# 05_SD_USB.net
KiCad netlist of a schematic drawn in Altium Designer
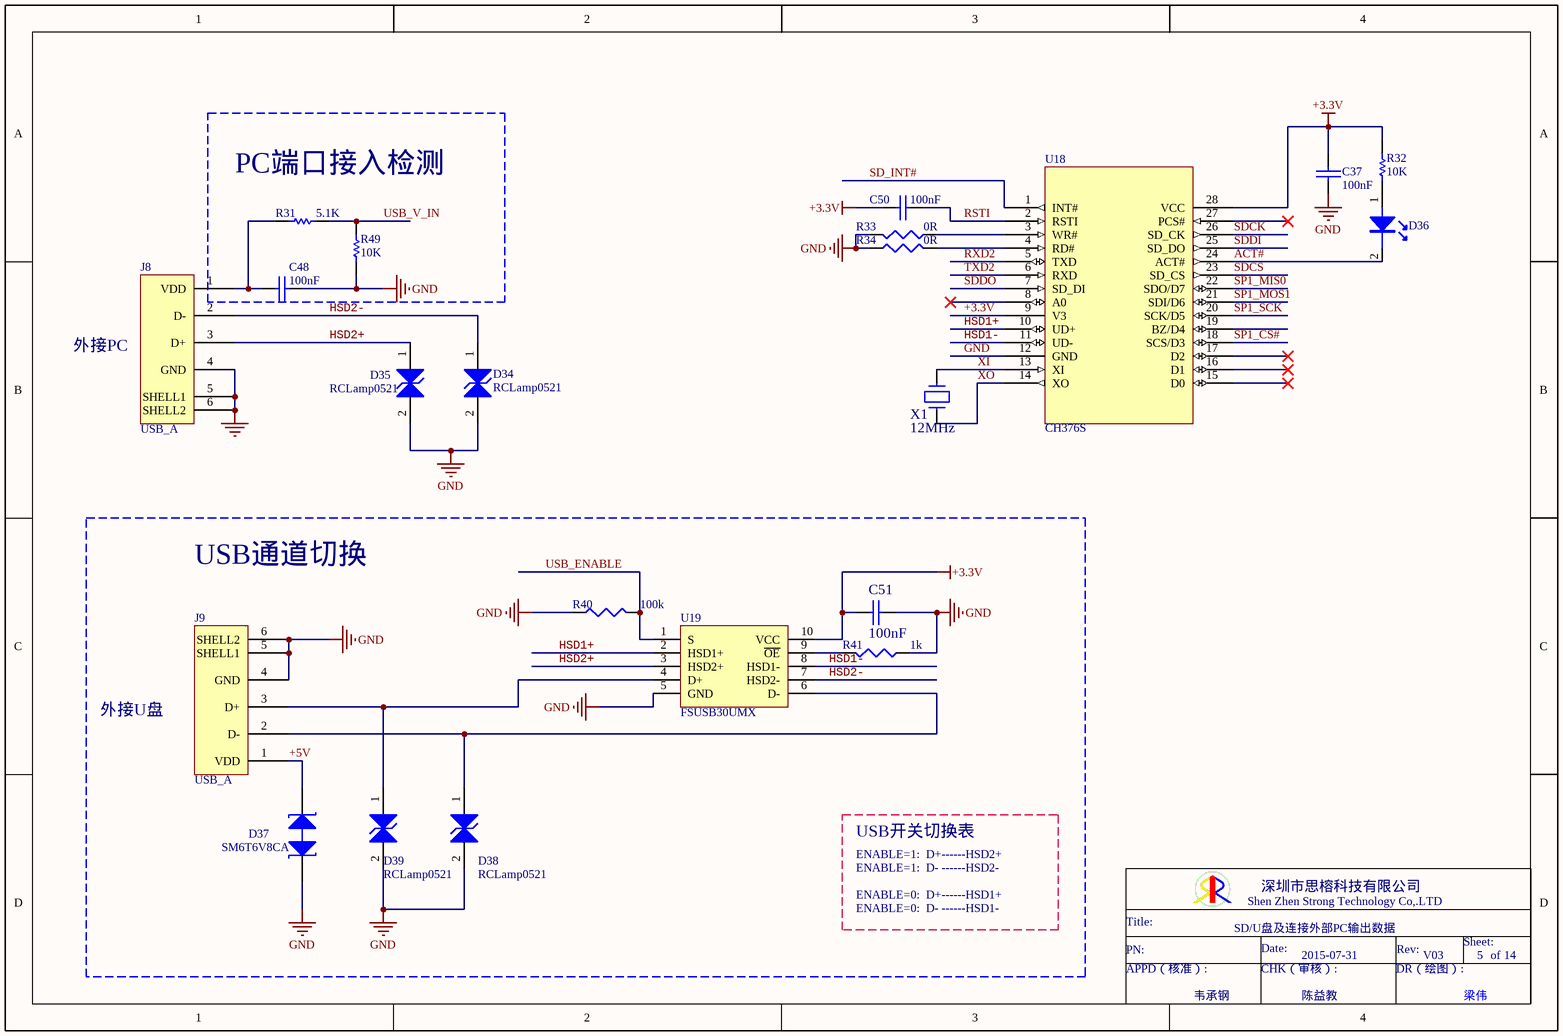
[diagram p0: 05_SD_USB.SchDoc]

(export (version "E")
  (design (tool "Eeschema 10.0.6"))
  (components
    (comp (ref "C37")
      (value "100nF")
      (footprint "0603C")
      (description "Capacitor")
      (libsource (lib "*") (part "CAP"))
    )
    (comp (ref "C48")
      (value "100nF")
      (footprint "0603C")
      (description "Capacitor")
      (libsource (lib "Mylibrary") (part "CAP"))
    )
    (comp (ref "C50")
      (value "100nF")
      (footprint "0603C")
      (description "Capacitor")
      (libsource (lib "Mylibrary") (part "CAP"))
    )
    (comp (ref "C51") (value "100nF") (footprint "0603C") (libsource (lib "*") (part "Pro7B.tmp_0.01u_17")))
    (comp (ref "D34")
      (value "RCLamp0521")
      (footprint "TVS")
      (description "RCLamp0521   SEMTECH")
      (fields (field (name "PUBLISHER") "Altium Limited"))
      (libsource (lib "LGA") (part "TVS"))
    )
    (comp (ref "D35")
      (value "RCLamp0521")
      (footprint "TVS")
      (description "RCLamp0521   SEMTECH")
      (fields (field (name "PUBLISHER") "Altium Limited"))
      (libsource (lib "LGA") (part "TVS"))
    )
    (comp (ref "D36")
      (value "LED灯 白发红光")
      (footprint "D0603")
      (description "LED灯")
      (libsource (lib "Mylibrary") (part "LED"))
    )
    (comp (ref "D37")
      (value "SM6T6V8CA")
      (footprint "DO-214AA")
      (description "SM6T6V8CA  ST")
      (fields (field (name "PUBLISHER") "Altium Limited"))
      (libsource (lib "Mylibrary") (part "TVS-1"))
    )
    (comp (ref "D38")
      (value "RCLamp0521")
      (footprint "TVS")
      (description "RCLamp0521   SEMTECH")
      (fields (field (name "PUBLISHER") "Altium Limited"))
      (libsource (lib "LGA") (part "TVS"))
    )
    (comp (ref "D39")
      (value "RCLamp0521")
      (footprint "TVS")
      (description "RCLamp0521   SEMTECH")
      (fields (field (name "PUBLISHER") "Altium Limited"))
      (libsource (lib "LGA") (part "TVS"))
    )
    (comp (ref "J8") (value "USB_A") (footprint "USB-AF") (libsource (lib "*") (part "USB")))
    (comp (ref "J9") (value "USB_A") (footprint "USB-AF") (libsource (lib "") (part "USB_1")))
    (comp (ref "R31") (value "5.1K") (footprint "0603R") (libsource (lib "Mylibrary") (part "RES")))
    (comp (ref "R32") (value "10K") (footprint "0603R") (libsource (lib "Mylibrary") (part "RES")))
    (comp (ref "R33") (value "0R") (footprint "0603R") (libsource (lib "LGA") (part "RES1")))
    (comp (ref "R34") (value "0R") (footprint "0603R") (libsource (lib "LGA") (part "RES1")))
    (comp (ref "R40") (value "100k") (footprint "0603R") (libsource (lib "Mylibrary") (part "RES1")))
    (comp (ref "R41") (value "1k") (footprint "0603R") (libsource (lib "Mylibrary") (part "RES1")))
    (comp (ref "R49") (value "10K") (footprint "0603R") (libsource (lib "Mylibrary") (part "RES")))
    (comp (ref "U18")
      (value "CH376S")
      (footprint "SOP28")
      (description "USB Host and SD card Host with File System & USB Device for MCU, parallel / SPI / UART Serial")
      (libsource (lib "*") (part "CH376S"))
    )
    (comp (ref "U19")
      (value "FSUSB30UMX")
      (footprint "SSOP10")
      (description "USB开关")
      (libsource (lib "Mylibrary") (part "FSUSB30UMX_1"))
    )
    (comp (ref "X1") (value "12MHz") (footprint "CRYL3*5") (libsource (lib "*") (part "Pro7B.tmp_12MHz_19")))
  )
  (nets
    (net (code "1") (name "+3.3V") (class "Default")
      (node (ref "C37") (pin "1") (pinfunction "1_1") (pintype "passive"))
      (node (ref "C50") (pin "1") (pinfunction "1_1") (pintype "passive"))
      (node (ref "C51") (pin "1") (pintype "passive"))
      (node (ref "R32") (pin "2") (pinfunction "2_2") (pintype "passive"))
      (node (ref "U18") (pin "28") (pinfunction "VCC_28") (pintype "power_in"))
      (node (ref "U18") (pin "9") (pinfunction "V3_9") (pintype "power_in"))
      (node (ref "U19") (pin "10") (pinfunction "VCC_10") (pintype "power_in"))
    )
    (net (code "2") (name "/+5V") (class "Default")
      (node (ref "D37") (pin "2") (pinfunction "2_2") (pintype "passive"))
      (node (ref "J9") (pin "1") (pinfunction "VDD_1") (pintype "passive"))
    )
    (net (code "3") (name "/ACT#") (class "Default")
      (node (ref "D36") (pin "2") (pinfunction "2_2") (pintype "passive"))
      (node (ref "U18") (pin "24") (pinfunction "ACT#_24") (pintype "output"))
    )
    (net (code "4") (name "/HSD1+") (class "Default")
      (node (ref "U18") (pin "10") (pinfunction "UD+_10") (pintype "bidirectional"))
      (node (ref "U19") (pin "2") (pinfunction "HSD1+_2") (pintype "passive"))
    )
    (net (code "5") (name "/HSD1-") (class "Default")
      (node (ref "U18") (pin "11") (pinfunction "UD-_11") (pintype "bidirectional"))
      (node (ref "U19") (pin "8") (pinfunction "HSD1-_8") (pintype "passive"))
    )
    (net (code "6") (name "/HSD2+") (class "Default")
      (node (ref "D35") (pin "1") (pinfunction "1_1") (pintype "passive"))
      (node (ref "J8") (pin "3") (pinfunction "D+_3") (pintype "passive"))
      (node (ref "U19") (pin "3") (pinfunction "HSD2+_3") (pintype "passive"))
    )
    (net (code "7") (name "/HSD2-") (class "Default")
      (node (ref "D34") (pin "1") (pinfunction "1_1") (pintype "passive"))
      (node (ref "J8") (pin "2") (pinfunction "D-_2") (pintype "passive"))
      (node (ref "U19") (pin "7") (pinfunction "HSD2-_7") (pintype "passive"))
    )
    (net (code "8") (name "/RSTI") (class "Default")
      (node (ref "C50") (pin "2") (pinfunction "2_2") (pintype "passive"))
      (node (ref "U18") (pin "2") (pinfunction "RSTI_2") (pintype "input"))
    )
    (net (code "9") (name "/RXD2") (class "Default")
      (node (ref "U18") (pin "5") (pinfunction "TXD_5") (pintype "bidirectional"))
    )
    (net (code "10") (name "/SDCK") (class "Default")
      (node (ref "U18") (pin "26") (pinfunction "SD_CK_26") (pintype "output"))
    )
    (net (code "11") (name "/SDCS") (class "Default")
      (node (ref "U18") (pin "23") (pinfunction "SD_CS_23") (pintype "output"))
    )
    (net (code "12") (name "/SDDI") (class "Default")
      (node (ref "U18") (pin "25") (pinfunction "SD_DO_25") (pintype "output"))
    )
    (net (code "13") (name "/SDDO") (class "Default")
      (node (ref "U18") (pin "7") (pinfunction "SD_DI_7") (pintype "input"))
    )
    (net (code "14") (name "/SD_INT#") (class "Default")
      (node (ref "U18") (pin "1") (pinfunction "INT#_1") (pintype "output"))
    )
    (net (code "15") (name "/SP1_CS#") (class "Default")
      (node (ref "U18") (pin "18") (pinfunction "SCS/D3_18") (pintype "bidirectional"))
    )
    (net (code "16") (name "/SP1_MIS0") (class "Default")
      (node (ref "U18") (pin "22") (pinfunction "SDO/D7_22") (pintype "bidirectional"))
    )
    (net (code "17") (name "/SP1_MOS1") (class "Default")
      (node (ref "U18") (pin "21") (pinfunction "SDI/D6_21") (pintype "bidirectional"))
    )
    (net (code "18") (name "/SP1_SCK") (class "Default")
      (node (ref "U18") (pin "20") (pinfunction "SCK/D5_20") (pintype "bidirectional"))
    )
    (net (code "19") (name "/TXD2") (class "Default")
      (node (ref "U18") (pin "6") (pinfunction "RXD_6") (pintype "input"))
    )
    (net (code "20") (name "/USB_ENABLE") (class "Default")
      (node (ref "R40") (pin "2") (pinfunction "2_2") (pintype "passive"))
      (node (ref "U19") (pin "1") (pinfunction "S_1") (pintype "passive"))
    )
    (net (code "21") (name "/USB_V_IN") (class "Default")
      (node (ref "R31") (pin "2") (pinfunction "2_2") (pintype "passive"))
      (node (ref "R49") (pin "1") (pinfunction "1_1") (pintype "passive"))
    )
    (net (code "22") (name "/XI") (class "Default")
      (node (ref "U18") (pin "13") (pinfunction "XI_13") (pintype "input"))
      (node (ref "X1") (pin "1") (pintype "passive"))
    )
    (net (code "23") (name "/XO") (class "Default")
      (node (ref "U18") (pin "14") (pinfunction "XO_14") (pintype "output"))
      (node (ref "X1") (pin "2") (pintype "passive"))
    )
    (net (code "24") (name "GND") (class "Default")
      (node (ref "C37") (pin "2") (pinfunction "2_2") (pintype "passive"))
      (node (ref "C48") (pin "2") (pinfunction "2_2") (pintype "passive"))
      (node (ref "C51") (pin "2") (pintype "passive"))
      (node (ref "D34") (pin "2") (pinfunction "2_2") (pintype "passive"))
      (node (ref "D35") (pin "2") (pinfunction "2_2") (pintype "passive"))
      (node (ref "D37") (pin "1") (pinfunction "1_1") (pintype "passive"))
      (node (ref "D38") (pin "2") (pinfunction "2_2") (pintype "passive"))
      (node (ref "D39") (pin "2") (pinfunction "2_2") (pintype "passive"))
      (node (ref "J8") (pin "4") (pinfunction "GND_4") (pintype "passive"))
      (node (ref "J8") (pin "5") (pinfunction "SHELL1_5") (pintype "passive"))
      (node (ref "J8") (pin "6") (pinfunction "SHELL2_6") (pintype "passive"))
      (node (ref "J9") (pin "4") (pinfunction "GND_4") (pintype "passive"))
      (node (ref "J9") (pin "5") (pinfunction "SHELL1_5") (pintype "passive"))
      (node (ref "J9") (pin "6") (pinfunction "SHELL2_6") (pintype "passive"))
      (node (ref "R33") (pin "2") (pinfunction "2_2") (pintype "passive"))
      (node (ref "R34") (pin "1") (pinfunction "1_1") (pintype "passive"))
      (node (ref "R40") (pin "1") (pinfunction "1_1") (pintype "passive"))
      (node (ref "R41") (pin "1") (pinfunction "1_1") (pintype "passive"))
      (node (ref "R49") (pin "2") (pinfunction "2_2") (pintype "passive"))
      (node (ref "U18") (pin "12") (pinfunction "GND_12") (pintype "power_in"))
      (node (ref "U19") (pin "5") (pinfunction "GND_5") (pintype "power_in"))
    )
    (net (code "25") (name "Net-(D36-Pad1)") (class "Default")
      (node (ref "D36") (pin "1") (pinfunction "1_1") (pintype "passive"))
      (node (ref "R32") (pin "1") (pinfunction "1_1") (pintype "passive"))
    )
    (net (code "26") (name "Net-(J8-VDD)") (class "Default")
      (node (ref "C48") (pin "1") (pinfunction "1_1") (pintype "passive"))
      (node (ref "J8") (pin "1") (pinfunction "VDD_1") (pintype "passive"))
      (node (ref "R31") (pin "1") (pinfunction "1_1") (pintype "passive"))
    )
    (net (code "27") (name "Net-(J9-D+)") (class "Default")
      (node (ref "D39") (pin "1") (pinfunction "1_1") (pintype "passive"))
      (node (ref "J9") (pin "3") (pinfunction "D+_3") (pintype "passive"))
      (node (ref "U19") (pin "4") (pinfunction "D+_4") (pintype "passive"))
    )
    (net (code "28") (name "Net-(J9-D-)") (class "Default")
      (node (ref "D38") (pin "1") (pinfunction "1_1") (pintype "passive"))
      (node (ref "J9") (pin "2") (pinfunction "D-_2") (pintype "passive"))
      (node (ref "U19") (pin "6") (pinfunction "D-_6") (pintype "passive"))
    )
    (net (code "29") (name "Net-(U18-RD#)") (class "Default")
      (node (ref "R34") (pin "2") (pinfunction "2_2") (pintype "passive"))
      (node (ref "U18") (pin "4") (pinfunction "RD#_4") (pintype "input"))
    )
    (net (code "30") (name "Net-(U18-WR#)") (class "Default")
      (node (ref "R33") (pin "1") (pinfunction "1_1") (pintype "passive"))
      (node (ref "U18") (pin "3") (pinfunction "WR#_3") (pintype "input"))
    )
    (net (code "31") (name "Net-(U19-~{OE})") (class "Default")
      (node (ref "R41") (pin "2") (pinfunction "2_2") (pintype "passive"))
      (node (ref "U19") (pin "9") (pinfunction "~{OE}_9") (pintype "passive"))
    )
    (net (code "32") (name "unconnected-(U18-A0-Pad8)") (class "Default")
      (node (ref "U18") (pin "8") (pinfunction "A0_8") (pintype "bidirectional+no_connect"))
    )
    (net (code "33") (name "unconnected-(U18-BZ{slash}D4-Pad19)") (class "Default")
      (node (ref "U18") (pin "19") (pinfunction "BZ/D4_19") (pintype "bidirectional"))
    )
    (net (code "34") (name "unconnected-(U18-D0-Pad15)") (class "Default")
      (node (ref "U18") (pin "15") (pinfunction "D0_15") (pintype "bidirectional+no_connect"))
    )
    (net (code "35") (name "unconnected-(U18-D1-Pad16)") (class "Default")
      (node (ref "U18") (pin "16") (pinfunction "D1_16") (pintype "bidirectional+no_connect"))
    )
    (net (code "36") (name "unconnected-(U18-D2-Pad17)") (class "Default")
      (node (ref "U18") (pin "17") (pinfunction "D2_17") (pintype "bidirectional+no_connect"))
    )
    (net (code "37") (name "unconnected-(U18-PCS#-Pad27)") (class "Default")
      (node (ref "U18") (pin "27") (pinfunction "PCS#_27") (pintype "input+no_connect"))
    )
  )
)
